# 16_FE_PORT_9-16.net
KiCad netlist of a schematic drawn in Altium Designer
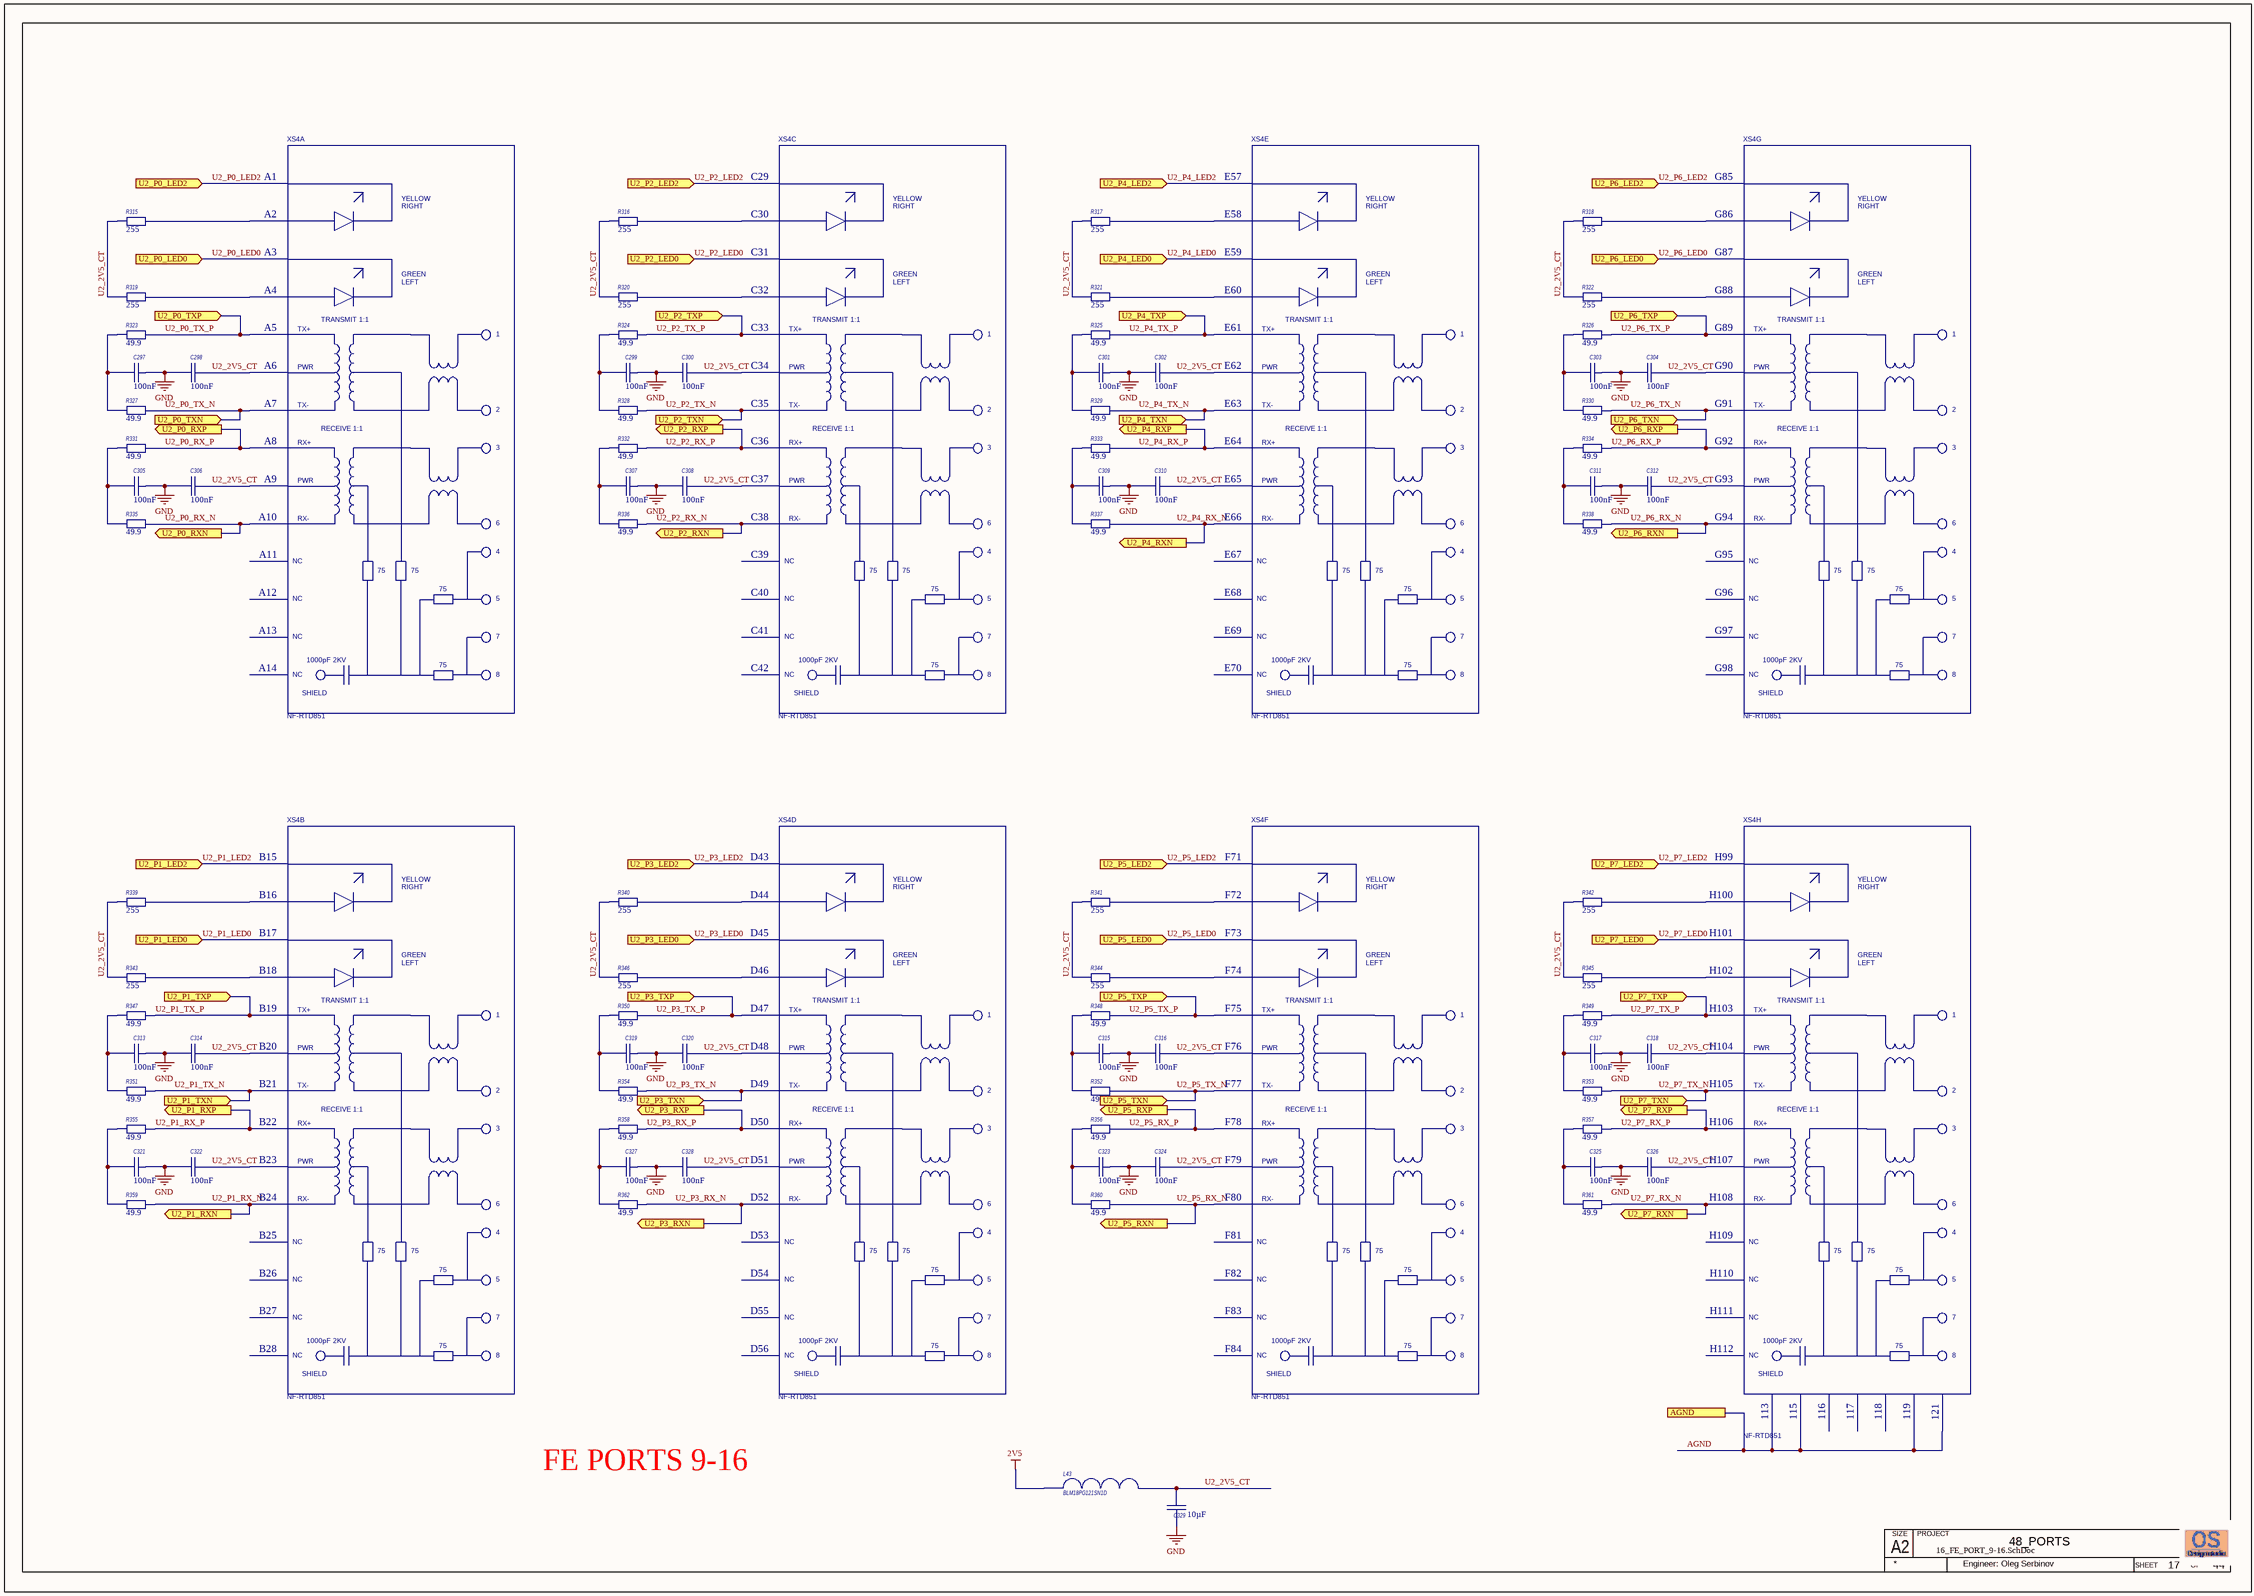
[diagram p0: 16_FE_PORT_9-16.SchDoc]

(export (version "E")
  (design (tool "Eeschema 10.0.6"))
  (components
    (comp (ref "C297")
      (value "GRM155R71E104KE14D")
      (footprint "C0402_IPC High Density")
      (description "C0402, 100nF, 25V, X7R")
      (fields
        (field (name "MANUFACTURER") "Murata")
        (field (name "CAPACITANCE") "100nF")
        (field (name "CUSTOMER PART NUMBER") "Конденсатор, 100n, 0402, 25V, X7R, 10%")
      )
      (libsource (lib "CAPACITORS") (part "GRM155R71E104KE14D"))
    )
    (comp (ref "C298")
      (value "GRM155R71E104KE14D")
      (footprint "C0402_IPC High Density")
      (description "C0402, 100nF, 25V, X7R")
      (fields
        (field (name "MANUFACTURER") "Murata")
        (field (name "CAPACITANCE") "100nF")
        (field (name "CUSTOMER PART NUMBER") "Конденсатор, 100n, 0402, 25V, X7R, 10%")
      )
      (libsource (lib "CAPACITORS") (part "GRM155R71E104KE14D"))
    )
    (comp (ref "C299")
      (value "GRM155R71E104KE14D")
      (footprint "C0402_IPC High Density")
      (description "C0402, 100nF, 25V, X7R")
      (fields
        (field (name "MANUFACTURER") "Murata")
        (field (name "CAPACITANCE") "100nF")
        (field (name "CUSTOMER PART NUMBER") "Конденсатор, 100n, 0402, 25V, X7R, 10%")
      )
      (libsource (lib "CAPACITORS") (part "GRM155R71E104KE14D"))
    )
    (comp (ref "C300")
      (value "GRM155R71E104KE14D")
      (footprint "C0402_IPC High Density")
      (description "C0402, 100nF, 25V, X7R")
      (fields
        (field (name "MANUFACTURER") "Murata")
        (field (name "CAPACITANCE") "100nF")
        (field (name "CUSTOMER PART NUMBER") "Конденсатор, 100n, 0402, 25V, X7R, 10%")
      )
      (libsource (lib "CAPACITORS") (part "GRM155R71E104KE14D"))
    )
    (comp (ref "C301")
      (value "GRM155R71E104KE14D")
      (footprint "C0402_IPC High Density")
      (description "C0402, 100nF, 25V, X7R")
      (fields
        (field (name "MANUFACTURER") "Murata")
        (field (name "CAPACITANCE") "100nF")
        (field (name "CUSTOMER PART NUMBER") "Конденсатор, 100n, 0402, 25V, X7R, 10%")
      )
      (libsource (lib "CAPACITORS") (part "GRM155R71E104KE14D"))
    )
    (comp (ref "C302")
      (value "GRM155R71E104KE14D")
      (footprint "C0402_IPC High Density")
      (description "C0402, 100nF, 25V, X7R")
      (fields
        (field (name "MANUFACTURER") "Murata")
        (field (name "CAPACITANCE") "100nF")
        (field (name "CUSTOMER PART NUMBER") "Конденсатор, 100n, 0402, 25V, X7R, 10%")
      )
      (libsource (lib "CAPACITORS") (part "GRM155R71E104KE14D"))
    )
    (comp (ref "C303")
      (value "GRM155R71E104KE14D")
      (footprint "C0402_IPC High Density")
      (description "C0402, 100nF, 25V, X7R")
      (fields
        (field (name "MANUFACTURER") "Murata")
        (field (name "CAPACITANCE") "100nF")
        (field (name "CUSTOMER PART NUMBER") "Конденсатор, 100n, 0402, 25V, X7R, 10%")
      )
      (libsource (lib "CAPACITORS") (part "GRM155R71E104KE14D"))
    )
    (comp (ref "C304")
      (value "GRM155R71E104KE14D")
      (footprint "C0402_IPC High Density")
      (description "C0402, 100nF, 25V, X7R")
      (fields
        (field (name "MANUFACTURER") "Murata")
        (field (name "CAPACITANCE") "100nF")
        (field (name "CUSTOMER PART NUMBER") "Конденсатор, 100n, 0402, 25V, X7R, 10%")
      )
      (libsource (lib "CAPACITORS") (part "GRM155R71E104KE14D"))
    )
    (comp (ref "C305")
      (value "GRM155R71E104KE14D")
      (footprint "C0402_IPC High Density")
      (description "C0402, 100nF, 25V, X7R")
      (fields
        (field (name "MANUFACTURER") "Murata")
        (field (name "CAPACITANCE") "100nF")
        (field (name "CUSTOMER PART NUMBER") "Конденсатор, 100n, 0402, 25V, X7R, 10%")
      )
      (libsource (lib "CAPACITORS") (part "GRM155R71E104KE14D"))
    )
    (comp (ref "C306")
      (value "GRM155R71E104KE14D")
      (footprint "C0402_IPC High Density")
      (description "C0402, 100nF, 25V, X7R")
      (fields
        (field (name "MANUFACTURER") "Murata")
        (field (name "CAPACITANCE") "100nF")
        (field (name "CUSTOMER PART NUMBER") "Конденсатор, 100n, 0402, 25V, X7R, 10%")
      )
      (libsource (lib "CAPACITORS") (part "GRM155R71E104KE14D"))
    )
    (comp (ref "C307")
      (value "GRM155R71E104KE14D")
      (footprint "C0402_IPC High Density")
      (description "C0402, 100nF, 25V, X7R")
      (fields
        (field (name "MANUFACTURER") "Murata")
        (field (name "CAPACITANCE") "100nF")
        (field (name "CUSTOMER PART NUMBER") "Конденсатор, 100n, 0402, 25V, X7R, 10%")
      )
      (libsource (lib "CAPACITORS") (part "GRM155R71E104KE14D"))
    )
    (comp (ref "C308")
      (value "GRM155R71E104KE14D")
      (footprint "C0402_IPC High Density")
      (description "C0402, 100nF, 25V, X7R")
      (fields
        (field (name "MANUFACTURER") "Murata")
        (field (name "CAPACITANCE") "100nF")
        (field (name "CUSTOMER PART NUMBER") "Конденсатор, 100n, 0402, 25V, X7R, 10%")
      )
      (libsource (lib "CAPACITORS") (part "GRM155R71E104KE14D"))
    )
    (comp (ref "C309")
      (value "GRM155R71E104KE14D")
      (footprint "C0402_IPC High Density")
      (description "C0402, 100nF, 25V, X7R")
      (fields
        (field (name "MANUFACTURER") "Murata")
        (field (name "CAPACITANCE") "100nF")
        (field (name "CUSTOMER PART NUMBER") "Конденсатор, 100n, 0402, 25V, X7R, 10%")
      )
      (libsource (lib "CAPACITORS") (part "GRM155R71E104KE14D"))
    )
    (comp (ref "C310")
      (value "GRM155R71E104KE14D")
      (footprint "C0402_IPC High Density")
      (description "C0402, 100nF, 25V, X7R")
      (fields
        (field (name "MANUFACTURER") "Murata")
        (field (name "CAPACITANCE") "100nF")
        (field (name "CUSTOMER PART NUMBER") "Конденсатор, 100n, 0402, 25V, X7R, 10%")
      )
      (libsource (lib "CAPACITORS") (part "GRM155R71E104KE14D"))
    )
    (comp (ref "C311")
      (value "GRM155R71E104KE14D")
      (footprint "C0402_IPC High Density")
      (description "C0402, 100nF, 25V, X7R")
      (fields
        (field (name "MANUFACTURER") "Murata")
        (field (name "CAPACITANCE") "100nF")
        (field (name "CUSTOMER PART NUMBER") "Конденсатор, 100n, 0402, 25V, X7R, 10%")
      )
      (libsource (lib "CAPACITORS") (part "GRM155R71E104KE14D"))
    )
    (comp (ref "C312")
      (value "GRM155R71E104KE14D")
      (footprint "C0402_IPC High Density")
      (description "C0402, 100nF, 25V, X7R")
      (fields
        (field (name "MANUFACTURER") "Murata")
        (field (name "CAPACITANCE") "100nF")
        (field (name "CUSTOMER PART NUMBER") "Конденсатор, 100n, 0402, 25V, X7R, 10%")
      )
      (libsource (lib "CAPACITORS") (part "GRM155R71E104KE14D"))
    )
    (comp (ref "C313")
      (value "GRM155R71E104KE14D")
      (footprint "C0402_IPC High Density")
      (description "C0402, 100nF, 25V, X7R")
      (fields
        (field (name "MANUFACTURER") "Murata")
        (field (name "CAPACITANCE") "100nF")
        (field (name "CUSTOMER PART NUMBER") "Конденсатор, 100n, 0402, 25V, X7R, 10%")
      )
      (libsource (lib "CAPACITORS") (part "GRM155R71E104KE14D"))
    )
    (comp (ref "C314")
      (value "GRM155R71E104KE14D")
      (footprint "C0402_IPC High Density")
      (description "C0402, 100nF, 25V, X7R")
      (fields
        (field (name "MANUFACTURER") "Murata")
        (field (name "CAPACITANCE") "100nF")
        (field (name "CUSTOMER PART NUMBER") "Конденсатор, 100n, 0402, 25V, X7R, 10%")
      )
      (libsource (lib "CAPACITORS") (part "GRM155R71E104KE14D"))
    )
    (comp (ref "C315")
      (value "GRM155R71E104KE14D")
      (footprint "C0402_IPC High Density")
      (description "C0402, 100nF, 25V, X7R")
      (fields
        (field (name "MANUFACTURER") "Murata")
        (field (name "CAPACITANCE") "100nF")
        (field (name "CUSTOMER PART NUMBER") "Конденсатор, 100n, 0402, 25V, X7R, 10%")
      )
      (libsource (lib "CAPACITORS") (part "GRM155R71E104KE14D"))
    )
    (comp (ref "C316")
      (value "GRM155R71E104KE14D")
      (footprint "C0402_IPC High Density")
      (description "C0402, 100nF, 25V, X7R")
      (fields
        (field (name "MANUFACTURER") "Murata")
        (field (name "CAPACITANCE") "100nF")
        (field (name "CUSTOMER PART NUMBER") "Конденсатор, 100n, 0402, 25V, X7R, 10%")
      )
      (libsource (lib "CAPACITORS") (part "GRM155R71E104KE14D"))
    )
    (comp (ref "C317")
      (value "GRM155R71E104KE14D")
      (footprint "C0402_IPC High Density")
      (description "C0402, 100nF, 25V, X7R")
      (fields
        (field (name "MANUFACTURER") "Murata")
        (field (name "CAPACITANCE") "100nF")
        (field (name "CUSTOMER PART NUMBER") "Конденсатор, 100n, 0402, 25V, X7R, 10%")
      )
      (libsource (lib "CAPACITORS") (part "GRM155R71E104KE14D"))
    )
    (comp (ref "C318")
      (value "GRM155R71E104KE14D")
      (footprint "C0402_IPC High Density")
      (description "C0402, 100nF, 25V, X7R")
      (fields
        (field (name "MANUFACTURER") "Murata")
        (field (name "CAPACITANCE") "100nF")
        (field (name "CUSTOMER PART NUMBER") "Конденсатор, 100n, 0402, 25V, X7R, 10%")
      )
      (libsource (lib "CAPACITORS") (part "GRM155R71E104KE14D"))
    )
    (comp (ref "C319")
      (value "GRM155R71E104KE14D")
      (footprint "C0402_IPC High Density")
      (description "C0402, 100nF, 25V, X7R")
      (fields
        (field (name "MANUFACTURER") "Murata")
        (field (name "CAPACITANCE") "100nF")
        (field (name "CUSTOMER PART NUMBER") "Конденсатор, 100n, 0402, 25V, X7R, 10%")
      )
      (libsource (lib "CAPACITORS") (part "GRM155R71E104KE14D"))
    )
    (comp (ref "C320")
      (value "GRM155R71E104KE14D")
      (footprint "C0402_IPC High Density")
      (description "C0402, 100nF, 25V, X7R")
      (fields
        (field (name "MANUFACTURER") "Murata")
        (field (name "CAPACITANCE") "100nF")
        (field (name "CUSTOMER PART NUMBER") "Конденсатор, 100n, 0402, 25V, X7R, 10%")
      )
      (libsource (lib "CAPACITORS") (part "GRM155R71E104KE14D"))
    )
    (comp (ref "C321")
      (value "GRM155R71E104KE14D")
      (footprint "C0402_IPC High Density")
      (description "C0402, 100nF, 25V, X7R")
      (fields
        (field (name "MANUFACTURER") "Murata")
        (field (name "CAPACITANCE") "100nF")
        (field (name "CUSTOMER PART NUMBER") "Конденсатор, 100n, 0402, 25V, X7R, 10%")
      )
      (libsource (lib "CAPACITORS") (part "GRM155R71E104KE14D"))
    )
    (comp (ref "C322")
      (value "GRM155R71E104KE14D")
      (footprint "C0402_IPC High Density")
      (description "C0402, 100nF, 25V, X7R")
      (fields
        (field (name "MANUFACTURER") "Murata")
        (field (name "CAPACITANCE") "100nF")
        (field (name "CUSTOMER PART NUMBER") "Конденсатор, 100n, 0402, 25V, X7R, 10%")
      )
      (libsource (lib "CAPACITORS") (part "GRM155R71E104KE14D"))
    )
    (comp (ref "C323")
      (value "GRM155R71E104KE14D")
      (footprint "C0402_IPC High Density")
      (description "C0402, 100nF, 25V, X7R")
      (fields
        (field (name "MANUFACTURER") "Murata")
        (field (name "CAPACITANCE") "100nF")
        (field (name "CUSTOMER PART NUMBER") "Конденсатор, 100n, 0402, 25V, X7R, 10%")
      )
      (libsource (lib "CAPACITORS") (part "GRM155R71E104KE14D"))
    )
    (comp (ref "C324")
      (value "GRM155R71E104KE14D")
      (footprint "C0402_IPC High Density")
      (description "C0402, 100nF, 25V, X7R")
      (fields
        (field (name "MANUFACTURER") "Murata")
        (field (name "CAPACITANCE") "100nF")
        (field (name "CUSTOMER PART NUMBER") "Конденсатор, 100n, 0402, 25V, X7R, 10%")
      )
      (libsource (lib "CAPACITORS") (part "GRM155R71E104KE14D"))
    )
    (comp (ref "C325")
      (value "GRM155R71E104KE14D")
      (footprint "C0402_IPC High Density")
      (description "C0402, 100nF, 25V, X7R")
      (fields
        (field (name "MANUFACTURER") "Murata")
        (field (name "CAPACITANCE") "100nF")
        (field (name "CUSTOMER PART NUMBER") "Конденсатор, 100n, 0402, 25V, X7R, 10%")
      )
      (libsource (lib "CAPACITORS") (part "GRM155R71E104KE14D"))
    )
    (comp (ref "C326")
      (value "GRM155R71E104KE14D")
      (footprint "C0402_IPC High Density")
      (description "C0402, 100nF, 25V, X7R")
      (fields
        (field (name "MANUFACTURER") "Murata")
        (field (name "CAPACITANCE") "100nF")
        (field (name "CUSTOMER PART NUMBER") "Конденсатор, 100n, 0402, 25V, X7R, 10%")
      )
      (libsource (lib "CAPACITORS") (part "GRM155R71E104KE14D"))
    )
    (comp (ref "C327")
      (value "GRM155R71E104KE14D")
      (footprint "C0402_IPC High Density")
      (description "C0402, 100nF, 25V, X7R")
      (fields
        (field (name "MANUFACTURER") "Murata")
        (field (name "CAPACITANCE") "100nF")
        (field (name "CUSTOMER PART NUMBER") "Конденсатор, 100n, 0402, 25V, X7R, 10%")
      )
      (libsource (lib "CAPACITORS") (part "GRM155R71E104KE14D"))
    )
    (comp (ref "C328")
      (value "GRM155R71E104KE14D")
      (footprint "C0402_IPC High Density")
      (description "C0402, 100nF, 25V, X7R")
      (fields
        (field (name "MANUFACTURER") "Murata")
        (field (name "CAPACITANCE") "100nF")
        (field (name "CUSTOMER PART NUMBER") "Конденсатор, 100n, 0402, 25V, X7R, 10%")
      )
      (libsource (lib "CAPACITORS") (part "GRM155R71E104KE14D"))
    )
    (comp (ref "C329")
      (value "GRM21BR61C106KE15")
      (footprint "CAPC2012[0805]")
      (description "C0805, 10uF 10%, 16V, X5R")
      (fields
        (field (name "MANUFACTURER") "Murata")
        (field (name "TOLERANCE") "±10%")
        (field (name "CAPACITANCE") "10µF")
      )
      (libsource (lib "CAPACITORS") (part "GRM21BR61C106KE15"))
    )
    (comp (ref "L43")
      (value "BLM18PG121SN1D")
      (footprint "INDC1608X95N")
      (description "FILTER BLM18 (0603, 2A)")
      (fields
        (field (name "MANUFACTURER") "Murata")
        (field (name "RPART NUMBER") "MPZ1608S121ATAH0 ; CIC10P121NC ; MPZ1608S121ATDH5 ; BLM18PG121SH1D ; 742792625")
      )
      (libsource (lib "INDUCTORS") (part "BLM18PG121SN1D"))
    )
    (comp (ref "R315")
      (value "ERJ-2RKF2550X")
      (footprint "RESC1005[0402]")
      (description "R0402, 255R 1%")
      (fields
        (field (name "MANUFACTURER") "Panasonic")
        (field (name "TOLERANCE") "±1%")
        (field (name "RESISTANCE (OHMS)") "255")
      )
      (libsource (lib "RESISTOR") (part "ERJ-2RKF2550X"))
    )
    (comp (ref "R316")
      (value "ERJ-2RKF2550X")
      (footprint "RESC1005[0402]")
      (description "R0402, 255R 1%")
      (fields
        (field (name "MANUFACTURER") "Panasonic")
        (field (name "TOLERANCE") "±1%")
        (field (name "RESISTANCE (OHMS)") "255")
      )
      (libsource (lib "RESISTOR") (part "ERJ-2RKF2550X"))
    )
    (comp (ref "R317")
      (value "ERJ-2RKF2550X")
      (footprint "RESC1005[0402]")
      (description "R0402, 255R 1%")
      (fields
        (field (name "MANUFACTURER") "Panasonic")
        (field (name "TOLERANCE") "±1%")
        (field (name "RESISTANCE (OHMS)") "255")
      )
      (libsource (lib "RESISTOR") (part "ERJ-2RKF2550X"))
    )
    (comp (ref "R318")
      (value "ERJ-2RKF2550X")
      (footprint "RESC1005[0402]")
      (description "R0402, 255R 1%")
      (fields
        (field (name "MANUFACTURER") "Panasonic")
        (field (name "TOLERANCE") "±1%")
        (field (name "RESISTANCE (OHMS)") "255")
      )
      (libsource (lib "RESISTOR") (part "ERJ-2RKF2550X"))
    )
    (comp (ref "R319")
      (value "ERJ-2RKF2550X")
      (footprint "RESC1005[0402]")
      (description "R0402, 255R 1%")
      (fields
        (field (name "MANUFACTURER") "Panasonic")
        (field (name "TOLERANCE") "±1%")
        (field (name "RESISTANCE (OHMS)") "255")
      )
      (libsource (lib "RESISTOR") (part "ERJ-2RKF2550X"))
    )
    (comp (ref "R320")
      (value "ERJ-2RKF2550X")
      (footprint "RESC1005[0402]")
      (description "R0402, 255R 1%")
      (fields
        (field (name "MANUFACTURER") "Panasonic")
        (field (name "TOLERANCE") "±1%")
        (field (name "RESISTANCE (OHMS)") "255")
      )
      (libsource (lib "RESISTOR") (part "ERJ-2RKF2550X"))
    )
    (comp (ref "R321")
      (value "ERJ-2RKF2550X")
      (footprint "RESC1005[0402]")
      (description "R0402, 255R 1%")
      (fields
        (field (name "MANUFACTURER") "Panasonic")
        (field (name "TOLERANCE") "±1%")
        (field (name "RESISTANCE (OHMS)") "255")
      )
      (libsource (lib "RESISTOR") (part "ERJ-2RKF2550X"))
    )
    (comp (ref "R322")
      (value "ERJ-2RKF2550X")
      (footprint "RESC1005[0402]")
      (description "R0402, 255R 1%")
      (fields
        (field (name "MANUFACTURER") "Panasonic")
        (field (name "TOLERANCE") "±1%")
        (field (name "RESISTANCE (OHMS)") "255")
      )
      (libsource (lib "RESISTOR") (part "ERJ-2RKF2550X"))
    )
    (comp (ref "R323")
      (value "ERJ-2RKF49R9X")
      (footprint "R0402_IPC High Density")
      (description "R0402, 49.9R 1%")
      (fields
        (field (name "MANUFACTURER") "Panasonic")
        (field (name "TOLERANCE") "1 %")
        (field (name "RESISTANCE") "49.9")
      )
      (libsource (lib "RESISTOR") (part "ERJ-2RKF49R9X"))
    )
    (comp (ref "R324")
      (value "ERJ-2RKF49R9X")
      (footprint "R0402_IPC High Density")
      (description "R0402, 49.9R 1%")
      (fields
        (field (name "MANUFACTURER") "Panasonic")
        (field (name "TOLERANCE") "1 %")
        (field (name "RESISTANCE") "49.9")
      )
      (libsource (lib "RESISTOR") (part "ERJ-2RKF49R9X"))
    )
    (comp (ref "R325")
      (value "ERJ-2RKF49R9X")
      (footprint "R0402_IPC High Density")
      (description "R0402, 49.9R 1%")
      (fields
        (field (name "MANUFACTURER") "Panasonic")
        (field (name "TOLERANCE") "1 %")
        (field (name "RESISTANCE") "49.9")
      )
      (libsource (lib "RESISTOR") (part "ERJ-2RKF49R9X"))
    )
    (comp (ref "R326")
      (value "ERJ-2RKF49R9X")
      (footprint "R0402_IPC High Density")
      (description "R0402, 49.9R 1%")
      (fields
        (field (name "MANUFACTURER") "Panasonic")
        (field (name "TOLERANCE") "1 %")
        (field (name "RESISTANCE") "49.9")
      )
      (libsource (lib "RESISTOR") (part "ERJ-2RKF49R9X"))
    )
    (comp (ref "R327")
      (value "ERJ-2RKF49R9X")
      (footprint "R0402_IPC High Density")
      (description "R0402, 49.9R 1%")
      (fields
        (field (name "MANUFACTURER") "Panasonic")
        (field (name "TOLERANCE") "1 %")
        (field (name "RESISTANCE") "49.9")
      )
      (libsource (lib "RESISTOR") (part "ERJ-2RKF49R9X"))
    )
    (comp (ref "R328")
      (value "ERJ-2RKF49R9X")
      (footprint "R0402_IPC High Density")
      (description "R0402, 49.9R 1%")
      (fields
        (field (name "MANUFACTURER") "Panasonic")
        (field (name "TOLERANCE") "1 %")
        (field (name "RESISTANCE") "49.9")
      )
      (libsource (lib "RESISTOR") (part "ERJ-2RKF49R9X"))
    )
    (comp (ref "R329")
      (value "ERJ-2RKF49R9X")
      (footprint "R0402_IPC High Density")
      (description "R0402, 49.9R 1%")
      (fields
        (field (name "MANUFACTURER") "Panasonic")
        (field (name "TOLERANCE") "1 %")
        (field (name "RESISTANCE") "49.9")
      )
      (libsource (lib "RESISTOR") (part "ERJ-2RKF49R9X"))
    )
    (comp (ref "R330")
      (value "ERJ-2RKF49R9X")
      (footprint "R0402_IPC High Density")
      (description "R0402, 49.9R 1%")
      (fields
        (field (name "MANUFACTURER") "Panasonic")
        (field (name "TOLERANCE") "1 %")
        (field (name "RESISTANCE") "49.9")
      )
      (libsource (lib "RESISTOR") (part "ERJ-2RKF49R9X"))
    )
    (comp (ref "R331")
      (value "ERJ-2RKF49R9X")
      (footprint "R0402_IPC High Density")
      (description "R0402, 49.9R 1%")
      (fields
        (field (name "MANUFACTURER") "Panasonic")
        (field (name "TOLERANCE") "1 %")
        (field (name "RESISTANCE") "49.9")
      )
      (libsource (lib "RESISTOR") (part "ERJ-2RKF49R9X"))
    )
    (comp (ref "R332")
      (value "ERJ-2RKF49R9X")
      (footprint "R0402_IPC High Density")
      (description "R0402, 49.9R 1%")
      (fields
        (field (name "MANUFACTURER") "Panasonic")
        (field (name "TOLERANCE") "1 %")
        (field (name "RESISTANCE") "49.9")
      )
      (libsource (lib "RESISTOR") (part "ERJ-2RKF49R9X"))
    )
    (comp (ref "R333")
      (value "ERJ-2RKF49R9X")
      (footprint "R0402_IPC High Density")
      (description "R0402, 49.9R 1%")
      (fields
        (field (name "MANUFACTURER") "Panasonic")
        (field (name "TOLERANCE") "1 %")
        (field (name "RESISTANCE") "49.9")
      )
      (libsource (lib "RESISTOR") (part "ERJ-2RKF49R9X"))
    )
    (comp (ref "R334")
      (value "ERJ-2RKF49R9X")
      (footprint "R0402_IPC High Density")
      (description "R0402, 49.9R 1%")
      (fields
        (field (name "MANUFACTURER") "Panasonic")
        (field (name "TOLERANCE") "1 %")
        (field (name "RESISTANCE") "49.9")
      )
      (libsource (lib "RESISTOR") (part "ERJ-2RKF49R9X"))
    )
    (comp (ref "R335")
      (value "ERJ-2RKF49R9X")
      (footprint "R0402_IPC High Density")
      (description "R0402, 49.9R 1%")
      (fields
        (field (name "MANUFACTURER") "Panasonic")
        (field (name "TOLERANCE") "1 %")
        (field (name "RESISTANCE") "49.9")
      )
      (libsource (lib "RESISTOR") (part "ERJ-2RKF49R9X"))
    )
    (comp (ref "R336")
      (value "ERJ-2RKF49R9X")
      (footprint "R0402_IPC High Density")
      (description "R0402, 49.9R 1%")
      (fields
        (field (name "MANUFACTURER") "Panasonic")
        (field (name "TOLERANCE") "1 %")
        (field (name "RESISTANCE") "49.9")
      )
      (libsource (lib "RESISTOR") (part "ERJ-2RKF49R9X"))
    )
    (comp (ref "R337")
      (value "ERJ-2RKF49R9X")
      (footprint "R0402_IPC High Density")
      (description "R0402, 49.9R 1%")
      (fields
        (field (name "MANUFACTURER") "Panasonic")
        (field (name "TOLERANCE") "1 %")
        (field (name "RESISTANCE") "49.9")
      )
      (libsource (lib "RESISTOR") (part "ERJ-2RKF49R9X"))
    )
    (comp (ref "R338")
      (value "ERJ-2RKF49R9X")
      (footprint "R0402_IPC High Density")
      (description "R0402, 49.9R 1%")
      (fields
        (field (name "MANUFACTURER") "Panasonic")
        (field (name "TOLERANCE") "1 %")
        (field (name "RESISTANCE") "49.9")
      )
      (libsource (lib "RESISTOR") (part "ERJ-2RKF49R9X"))
    )
    (comp (ref "R339")
      (value "ERJ-2RKF2550X")
      (footprint "RESC1005[0402]")
      (description "R0402, 255R 1%")
      (fields
        (field (name "MANUFACTURER") "Panasonic")
        (field (name "TOLERANCE") "±1%")
        (field (name "RESISTANCE (OHMS)") "255")
      )
      (libsource (lib "RESISTOR") (part "ERJ-2RKF2550X"))
    )
    (comp (ref "R340")
      (value "ERJ-2RKF2550X")
      (footprint "RESC1005[0402]")
      (description "R0402, 255R 1%")
      (fields
        (field (name "MANUFACTURER") "Panasonic")
        (field (name "TOLERANCE") "±1%")
        (field (name "RESISTANCE (OHMS)") "255")
      )
      (libsource (lib "RESISTOR") (part "ERJ-2RKF2550X"))
    )
    (comp (ref "R341")
      (value "ERJ-2RKF2550X")
      (footprint "RESC1005[0402]")
      (description "R0402, 255R 1%")
      (fields
        (field (name "MANUFACTURER") "Panasonic")
        (field (name "TOLERANCE") "±1%")
        (field (name "RESISTANCE (OHMS)") "255")
      )
      (libsource (lib "RESISTOR") (part "ERJ-2RKF2550X"))
    )
    (comp (ref "R342")
      (value "ERJ-2RKF2550X")
      (footprint "RESC1005[0402]")
      (description "R0402, 255R 1%")
      (fields
        (field (name "MANUFACTURER") "Panasonic")
        (field (name "TOLERANCE") "±1%")
        (field (name "RESISTANCE (OHMS)") "255")
      )
      (libsource (lib "RESISTOR") (part "ERJ-2RKF2550X"))
    )
    (comp (ref "R343")
      (value "ERJ-2RKF2550X")
      (footprint "RESC1005[0402]")
      (description "R0402, 255R 1%")
      (fields
        (field (name "MANUFACTURER") "Panasonic")
        (field (name "TOLERANCE") "±1%")
        (field (name "RESISTANCE (OHMS)") "255")
      )
      (libsource (lib "RESISTOR") (part "ERJ-2RKF2550X"))
    )
    (comp (ref "R344")
      (value "ERJ-2RKF2550X")
      (footprint "RESC1005[0402]")
      (description "R0402, 255R 1%")
      (fields
        (field (name "MANUFACTURER") "Panasonic")
        (field (name "TOLERANCE") "±1%")
        (field (name "RESISTANCE (OHMS)") "255")
      )
      (libsource (lib "RESISTOR") (part "ERJ-2RKF2550X"))
    )
    (comp (ref "R345")
      (value "ERJ-2RKF2550X")
      (footprint "RESC1005[0402]")
      (description "R0402, 255R 1%")
      (fields
        (field (name "MANUFACTURER") "Panasonic")
        (field (name "TOLERANCE") "±1%")
        (field (name "RESISTANCE (OHMS)") "255")
      )
      (libsource (lib "RESISTOR") (part "ERJ-2RKF2550X"))
    )
    (comp (ref "R346")
      (value "ERJ-2RKF2550X")
      (footprint "RESC1005[0402]")
      (description "R0402, 255R 1%")
      (fields
        (field (name "MANUFACTURER") "Panasonic")
        (field (name "TOLERANCE") "±1%")
        (field (name "RESISTANCE (OHMS)") "255")
      )
      (libsource (lib "RESISTOR") (part "ERJ-2RKF2550X"))
    )
    (comp (ref "R347")
      (value "ERJ-2RKF49R9X")
      (footprint "R0402_IPC High Density")
      (description "R0402, 49.9R 1%")
      (fields
        (field (name "MANUFACTURER") "Panasonic")
        (field (name "TOLERANCE") "1 %")
        (field (name "RESISTANCE") "49.9")
      )
      (libsource (lib "RESISTOR") (part "ERJ-2RKF49R9X"))
    )
    (comp (ref "R348")
      (value "ERJ-2RKF49R9X")
      (footprint "R0402_IPC High Density")
      (description "R0402, 49.9R 1%")
      (fields
        (field (name "MANUFACTURER") "Panasonic")
        (field (name "TOLERANCE") "1 %")
        (field (name "RESISTANCE") "49.9")
      )
      (libsource (lib "RESISTOR") (part "ERJ-2RKF49R9X"))
    )
    (comp (ref "R349")
      (value "ERJ-2RKF49R9X")
      (footprint "R0402_IPC High Density")
      (description "R0402, 49.9R 1%")
      (fields
        (field (name "MANUFACTURER") "Panasonic")
        (field (name "TOLERANCE") "1 %")
        (field (name "RESISTANCE") "49.9")
      )
      (libsource (lib "RESISTOR") (part "ERJ-2RKF49R9X"))
    )
    (comp (ref "R350")
      (value "ERJ-2RKF49R9X")
      (footprint "R0402_IPC High Density")
      (description "R0402, 49.9R 1%")
      (fields
        (field (name "MANUFACTURER") "Panasonic")
        (field (name "TOLERANCE") "1 %")
        (field (name "RESISTANCE") "49.9")
      )
      (libsource (lib "RESISTOR") (part "ERJ-2RKF49R9X"))
    )
    (comp (ref "R351")
      (value "ERJ-2RKF49R9X")
      (footprint "R0402_IPC High Density")
      (description "R0402, 49.9R 1%")
      (fields
        (field (name "MANUFACTURER") "Panasonic")
        (field (name "TOLERANCE") "1 %")
        (field (name "RESISTANCE") "49.9")
      )
      (libsource (lib "RESISTOR") (part "ERJ-2RKF49R9X"))
    )
    (comp (ref "R352")
      (value "ERJ-2RKF49R9X")
      (footprint "R0402_IPC High Density")
      (description "R0402, 49.9R 1%")
      (fields
        (field (name "MANUFACTURER") "Panasonic")
        (field (name "TOLERANCE") "1 %")
        (field (name "RESISTANCE") "49.9")
      )
      (libsource (lib "RESISTOR") (part "ERJ-2RKF49R9X"))
    )
    (comp (ref "R353")
      (value "ERJ-2RKF49R9X")
      (footprint "R0402_IPC High Density")
      (description "R0402, 49.9R 1%")
      (fields
        (field (name "MANUFACTURER") "Panasonic")
        (field (name "TOLERANCE") "1 %")
        (field (name "RESISTANCE") "49.9")
      )
      (libsource (lib "RESISTOR") (part "ERJ-2RKF49R9X"))
    )
    (comp (ref "R354")
      (value "ERJ-2RKF49R9X")
      (footprint "R0402_IPC High Density")
      (description "R0402, 49.9R 1%")
      (fields
        (field (name "MANUFACTURER") "Panasonic")
        (field (name "TOLERANCE") "1 %")
        (field (name "RESISTANCE") "49.9")
      )
      (libsource (lib "RESISTOR") (part "ERJ-2RKF49R9X"))
    )
    (comp (ref "R355")
      (value "ERJ-2RKF49R9X")
      (footprint "R0402_IPC High Density")
      (description "R0402, 49.9R 1%")
      (fields
        (field (name "MANUFACTURER") "Panasonic")
        (field (name "TOLERANCE") "1 %")
        (field (name "RESISTANCE") "49.9")
      )
      (libsource (lib "RESISTOR") (part "ERJ-2RKF49R9X"))
    )
    (comp (ref "R356")
      (value "ERJ-2RKF49R9X")
      (footprint "R0402_IPC High Density")
      (description "R0402, 49.9R 1%")
      (fields
        (field (name "MANUFACTURER") "Panasonic")
        (field (name "TOLERANCE") "1 %")
        (field (name "RESISTANCE") "49.9")
      )
      (libsource (lib "RESISTOR") (part "ERJ-2RKF49R9X"))
    )
    (comp (ref "R357")
      (value "ERJ-2RKF49R9X")
      (footprint "R0402_IPC High Density")
      (description "R0402, 49.9R 1%")
      (fields
        (field (name "MANUFACTURER") "Panasonic")
        (field (name "TOLERANCE") "1 %")
        (field (name "RESISTANCE") "49.9")
      )
      (libsource (lib "RESISTOR") (part "ERJ-2RKF49R9X"))
    )
    (comp (ref "R358")
      (value "ERJ-2RKF49R9X")
      (footprint "R0402_IPC High Density")
      (description "R0402, 49.9R 1%")
      (fields
        (field (name "MANUFACTURER") "Panasonic")
        (field (name "TOLERANCE") "1 %")
        (field (name "RESISTANCE") "49.9")
      )
      (libsource (lib "RESISTOR") (part "ERJ-2RKF49R9X"))
    )
    (comp (ref "R359")
      (value "ERJ-2RKF49R9X")
      (footprint "R0402_IPC High Density")
      (description "R0402, 49.9R 1%")
      (fields
        (field (name "MANUFACTURER") "Panasonic")
        (field (name "TOLERANCE") "1 %")
        (field (name "RESISTANCE") "49.9")
      )
      (libsource (lib "RESISTOR") (part "ERJ-2RKF49R9X"))
    )
    (comp (ref "R360")
      (value "ERJ-2RKF49R9X")
      (footprint "R0402_IPC High Density")
      (description "R0402, 49.9R 1%")
      (fields
        (field (name "MANUFACTURER") "Panasonic")
        (field (name "TOLERANCE") "1 %")
        (field (name "RESISTANCE") "49.9")
      )
      (libsource (lib "RESISTOR") (part "ERJ-2RKF49R9X"))
    )
    (comp (ref "R361")
      (value "ERJ-2RKF49R9X")
      (footprint "R0402_IPC High Density")
      (description "R0402, 49.9R 1%")
      (fields
        (field (name "MANUFACTURER") "Panasonic")
        (field (name "TOLERANCE") "1 %")
        (field (name "RESISTANCE") "49.9")
      )
      (libsource (lib "RESISTOR") (part "ERJ-2RKF49R9X"))
    )
    (comp (ref "R362")
      (value "ERJ-2RKF49R9X")
      (footprint "R0402_IPC High Density")
      (description "R0402, 49.9R 1%")
      (fields
        (field (name "MANUFACTURER") "Panasonic")
        (field (name "TOLERANCE") "1 %")
        (field (name "RESISTANCE") "49.9")
      )
      (libsource (lib "RESISTOR") (part "ERJ-2RKF49R9X"))
    )
    (comp (ref "XS4")
      (value "NF-RTD851")
      (footprint "NF-RTD851_2X4_LED_NF-RTD851_2X4_LED(Primary)")
      (description "Connector RJ45 100mb 8 ports and led  NF-RTD851")
      (fields
        (field (name "CUSTOMER PART NUMBER") "Разъем, NF-RTD851, CONN MAGJACK 8PORT 100 BASE-TX")
        (field (name "MANUFACTURER") "Shenzhen Newfly Electronics")
      )
      (libsource (lib "CONNECTORS") (part "NF-RTD851 2X4 EMI LED"))
    )
  )
  (nets
    (net (code "1") (name "/AGND") (class "Default")
      (node (ref "XS4") (pin "113") (pintype "passive"))
      (node (ref "XS4") (pin "115") (pintype "passive"))
      (node (ref "XS4") (pin "119") (pintype "passive"))
      (node (ref "XS4") (pin "121") (pintype "passive"))
    )
    (net (code "2") (name "/U2_2V5_CT") (class "Default")
      (node (ref "C298") (pin "2") (pintype "passive"))
      (node (ref "C300") (pin "2") (pintype "passive"))
      (node (ref "C302") (pin "2") (pintype "passive"))
      (node (ref "C304") (pin "2") (pintype "passive"))
      (node (ref "C306") (pin "2") (pintype "passive"))
      (node (ref "C308") (pin "2") (pintype "passive"))
      (node (ref "C310") (pin "2") (pintype "passive"))
      (node (ref "C312") (pin "2") (pintype "passive"))
      (node (ref "C314") (pin "2") (pintype "passive"))
      (node (ref "C316") (pin "2") (pintype "passive"))
      (node (ref "C318") (pin "2") (pintype "passive"))
      (node (ref "C320") (pin "2") (pintype "passive"))
      (node (ref "C322") (pin "2") (pintype "passive"))
      (node (ref "C324") (pin "2") (pintype "passive"))
      (node (ref "C326") (pin "2") (pintype "passive"))
      (node (ref "C328") (pin "2") (pintype "passive"))
      (node (ref "C329") (pin "2") (pintype "passive"))
      (node (ref "L43") (pin "2") (pinfunction "2_2") (pintype "passive"))
      (node (ref "R315") (pin "1") (pintype "passive"))
      (node (ref "R316") (pin "1") (pintype "passive"))
      (node (ref "R317") (pin "1") (pintype "passive"))
      (node (ref "R318") (pin "1") (pintype "passive"))
      (node (ref "R319") (pin "1") (pintype "passive"))
      (node (ref "R320") (pin "1") (pintype "passive"))
      (node (ref "R321") (pin "1") (pintype "passive"))
      (node (ref "R322") (pin "1") (pintype "passive"))
      (node (ref "R339") (pin "1") (pintype "passive"))
      (node (ref "R340") (pin "1") (pintype "passive"))
      (node (ref "R341") (pin "1") (pintype "passive"))
      (node (ref "R342") (pin "1") (pintype "passive"))
      (node (ref "R343") (pin "1") (pintype "passive"))
      (node (ref "R344") (pin "1") (pintype "passive"))
      (node (ref "R345") (pin "1") (pintype "passive"))
      (node (ref "R346") (pin "1") (pintype "passive"))
      (node (ref "XS4") (pin "A6") (pintype "passive"))
      (node (ref "XS4") (pin "A9") (pintype "passive"))
      (node (ref "XS4") (pin "B20") (pintype "passive"))
      (node (ref "XS4") (pin "B23") (pintype "passive"))
      (node (ref "XS4") (pin "C34") (pintype "passive"))
      (node (ref "XS4") (pin "C37") (pintype "passive"))
      (node (ref "XS4") (pin "D48") (pintype "passive"))
      (node (ref "XS4") (pin "D51") (pintype "passive"))
      (node (ref "XS4") (pin "E62") (pintype "passive"))
      (node (ref "XS4") (pin "E65") (pintype "passive"))
      (node (ref "XS4") (pin "F76") (pintype "passive"))
      (node (ref "XS4") (pin "F79") (pintype "passive"))
      (node (ref "XS4") (pin "G90") (pintype "passive"))
      (node (ref "XS4") (pin "G93") (pintype "passive"))
      (node (ref "XS4") (pin "H104") (pintype "passive"))
      (node (ref "XS4") (pin "H107") (pintype "passive"))
    )
    (net (code "3") (name "/U2_P0_LED0") (class "Default") (node (ref "XS4") (pin "A3") (pintype "passive")))
    (net (code "4") (name "/U2_P0_LED2") (class "Default") (node (ref "XS4") (pin "A1") (pintype "passive")))
    (net (code "5") (name "/U2_P0_RX_N") (class "Default")
      (node (ref "R335") (pin "2") (pintype "passive"))
      (node (ref "XS4") (pin "A10") (pintype "passive"))
    )
    (net (code "6") (name "/U2_P0_RX_P") (class "Default")
      (node (ref "R331") (pin "2") (pintype "passive"))
      (node (ref "XS4") (pin "A8") (pintype "passive"))
    )
    (net (code "7") (name "/U2_P0_TX_N") (class "Default")
      (node (ref "R327") (pin "2") (pintype "passive"))
      (node (ref "XS4") (pin "A7") (pintype "passive"))
    )
    (net (code "8") (name "/U2_P0_TX_P") (class "Default")
      (node (ref "R323") (pin "2") (pintype "passive"))
      (node (ref "XS4") (pin "A5") (pintype "passive"))
    )
    (net (code "9") (name "/U2_P1_LED0") (class "Default") (node (ref "XS4") (pin "B17") (pintype "passive")))
    (net (code "10") (name "/U2_P1_LED2") (class "Default")
      (node (ref "XS4") (pin "B15") (pintype "passive"))
    )
    (net (code "11") (name "/U2_P1_RX_N") (class "Default")
      (node (ref "R359") (pin "2") (pintype "passive"))
      (node (ref "XS4") (pin "B24") (pintype "passive"))
    )
    (net (code "12") (name "/U2_P1_RX_P") (class "Default")
      (node (ref "R355") (pin "2") (pintype "passive"))
      (node (ref "XS4") (pin "B22") (pintype "passive"))
    )
    (net (code "13") (name "/U2_P1_TX_N") (class "Default")
      (node (ref "R351") (pin "2") (pintype "passive"))
      (node (ref "XS4") (pin "B21") (pintype "passive"))
    )
    (net (code "14") (name "/U2_P1_TX_P") (class "Default")
      (node (ref "R347") (pin "2") (pintype "passive"))
      (node (ref "XS4") (pin "B19") (pintype "passive"))
    )
    (net (code "15") (name "/U2_P2_LED0") (class "Default")
      (node (ref "XS4") (pin "C31") (pintype "passive"))
    )
    (net (code "16") (name "/U2_P2_LED2") (class "Default")
      (node (ref "XS4") (pin "C29") (pintype "passive"))
    )
    (net (code "17") (name "/U2_P2_RX_N") (class "Default")
      (node (ref "R336") (pin "2") (pintype "passive"))
      (node (ref "XS4") (pin "C38") (pintype "passive"))
    )
    (net (code "18") (name "/U2_P2_RX_P") (class "Default")
      (node (ref "R332") (pin "2") (pintype "passive"))
      (node (ref "XS4") (pin "C36") (pintype "passive"))
    )
    (net (code "19") (name "/U2_P2_TX_N") (class "Default")
      (node (ref "R328") (pin "2") (pintype "passive"))
      (node (ref "XS4") (pin "C35") (pintype "passive"))
    )
    (net (code "20") (name "/U2_P2_TX_P") (class "Default")
      (node (ref "R324") (pin "2") (pintype "passive"))
      (node (ref "XS4") (pin "C33") (pintype "passive"))
    )
    (net (code "21") (name "/U2_P3_LED0") (class "Default")
      (node (ref "XS4") (pin "D45") (pintype "passive"))
    )
    (net (code "22") (name "/U2_P3_LED2") (class "Default")
      (node (ref "XS4") (pin "D43") (pintype "passive"))
    )
    (net (code "23") (name "/U2_P3_RX_N") (class "Default")
      (node (ref "R362") (pin "2") (pintype "passive"))
      (node (ref "XS4") (pin "D52") (pintype "passive"))
    )
    (net (code "24") (name "/U2_P3_RX_P") (class "Default")
      (node (ref "R358") (pin "2") (pintype "passive"))
      (node (ref "XS4") (pin "D50") (pintype "passive"))
    )
    (net (code "25") (name "/U2_P3_TX_N") (class "Default")
      (node (ref "R354") (pin "2") (pintype "passive"))
      (node (ref "XS4") (pin "D49") (pintype "passive"))
    )
    (net (code "26") (name "/U2_P3_TX_P") (class "Default")
      (node (ref "R350") (pin "2") (pintype "passive"))
      (node (ref "XS4") (pin "D47") (pintype "passive"))
    )
    (net (code "27") (name "/U2_P4_LED0") (class "Default")
      (node (ref "XS4") (pin "E59") (pintype "passive"))
    )
    (net (code "28") (name "/U2_P4_LED2") (class "Default")
      (node (ref "XS4") (pin "E57") (pintype "passive"))
    )
    (net (code "29") (name "/U2_P4_RX_N") (class "Default")
      (node (ref "R337") (pin "2") (pintype "passive"))
      (node (ref "XS4") (pin "E66") (pintype "passive"))
    )
    (net (code "30") (name "/U2_P4_RX_P") (class "Default")
      (node (ref "R333") (pin "2") (pintype "passive"))
      (node (ref "XS4") (pin "E64") (pintype "passive"))
    )
    (net (code "31") (name "/U2_P4_TX_N") (class "Default")
      (node (ref "R329") (pin "2") (pintype "passive"))
      (node (ref "XS4") (pin "E63") (pintype "passive"))
    )
    (net (code "32") (name "/U2_P4_TX_P") (class "Default")
      (node (ref "R325") (pin "2") (pintype "passive"))
      (node (ref "XS4") (pin "E61") (pintype "passive"))
    )
    (net (code "33") (name "/U2_P5_LED0") (class "Default")
      (node (ref "XS4") (pin "F73") (pintype "passive"))
    )
    (net (code "34") (name "/U2_P5_LED2") (class "Default")
      (node (ref "XS4") (pin "F71") (pintype "passive"))
    )
    (net (code "35") (name "/U2_P5_RX_N") (class "Default")
      (node (ref "R360") (pin "2") (pintype "passive"))
      (node (ref "XS4") (pin "F80") (pintype "passive"))
    )
    (net (code "36") (name "/U2_P5_RX_P") (class "Default")
      (node (ref "R356") (pin "2") (pintype "passive"))
      (node (ref "XS4") (pin "F78") (pintype "passive"))
    )
    (net (code "37") (name "/U2_P5_TX_N") (class "Default")
      (node (ref "R352") (pin "2") (pintype "passive"))
      (node (ref "XS4") (pin "F77") (pintype "passive"))
    )
    (net (code "38") (name "/U2_P5_TX_P") (class "Default")
      (node (ref "R348") (pin "2") (pintype "passive"))
      (node (ref "XS4") (pin "F75") (pintype "passive"))
    )
    (net (code "39") (name "/U2_P6_LED0") (class "Default")
      (node (ref "XS4") (pin "G87") (pintype "passive"))
    )
    (net (code "40") (name "/U2_P6_LED2") (class "Default")
      (node (ref "XS4") (pin "G85") (pintype "passive"))
    )
    (net (code "41") (name "/U2_P6_RX_N") (class "Default")
      (node (ref "R338") (pin "2") (pintype "passive"))
      (node (ref "XS4") (pin "G94") (pintype "passive"))
    )
    (net (code "42") (name "/U2_P6_RX_P") (class "Default")
      (node (ref "R334") (pin "2") (pintype "passive"))
      (node (ref "XS4") (pin "G92") (pintype "passive"))
    )
    (net (code "43") (name "/U2_P6_TX_N") (class "Default")
      (node (ref "R330") (pin "2") (pintype "passive"))
      (node (ref "XS4") (pin "G91") (pintype "passive"))
    )
    (net (code "44") (name "/U2_P6_TX_P") (class "Default")
      (node (ref "R326") (pin "2") (pintype "passive"))
      (node (ref "XS4") (pin "G89") (pintype "passive"))
    )
    (net (code "45") (name "/U2_P7_LED0") (class "Default")
      (node (ref "XS4") (pin "H101") (pintype "passive"))
    )
    (net (code "46") (name "/U2_P7_LED2") (class "Default")
      (node (ref "XS4") (pin "H99") (pintype "passive"))
    )
    (net (code "47") (name "/U2_P7_RX_N") (class "Default")
      (node (ref "R361") (pin "2") (pintype "passive"))
      (node (ref "XS4") (pin "H108") (pintype "passive"))
    )
    (net (code "48") (name "/U2_P7_RX_P") (class "Default")
      (node (ref "R357") (pin "2") (pintype "passive"))
      (node (ref "XS4") (pin "H106") (pintype "passive"))
    )
    (net (code "49") (name "/U2_P7_TX_N") (class "Default")
      (node (ref "R353") (pin "2") (pintype "passive"))
      (node (ref "XS4") (pin "H105") (pintype "passive"))
    )
    (net (code "50") (name "/U2_P7_TX_P") (class "Default")
      (node (ref "R349") (pin "2") (pintype "passive"))
      (node (ref "XS4") (pin "H103") (pintype "passive"))
    )
    (net (code "51") (name "2V5") (class "Default")
      (node (ref "L43") (pin "1") (pinfunction "1_1") (pintype "passive"))
    )
    (net (code "52") (name "GND") (class "Default")
      (node (ref "C297") (pin "2") (pintype "passive"))
      (node (ref "C298") (pin "1") (pintype "passive"))
      (node (ref "C299") (pin "2") (pintype "passive"))
      (node (ref "C300") (pin "1") (pintype "passive"))
      (node (ref "C301") (pin "2") (pintype "passive"))
      (node (ref "C302") (pin "1") (pintype "passive"))
      (node (ref "C303") (pin "2") (pintype "passive"))
      (node (ref "C304") (pin "1") (pintype "passive"))
      (node (ref "C305") (pin "2") (pintype "passive"))
      (node (ref "C306") (pin "1") (pintype "passive"))
      (node (ref "C307") (pin "2") (pintype "passive"))
      (node (ref "C308") (pin "1") (pintype "passive"))
      (node (ref "C309") (pin "2") (pintype "passive"))
      (node (ref "C310") (pin "1") (pintype "passive"))
      (node (ref "C311") (pin "2") (pintype "passive"))
      (node (ref "C312") (pin "1") (pintype "passive"))
      (node (ref "C313") (pin "2") (pintype "passive"))
      (node (ref "C314") (pin "1") (pintype "passive"))
      (node (ref "C315") (pin "2") (pintype "passive"))
      (node (ref "C316") (pin "1") (pintype "passive"))
      (node (ref "C317") (pin "2") (pintype "passive"))
      (node (ref "C318") (pin "1") (pintype "passive"))
      (node (ref "C319") (pin "2") (pintype "passive"))
      (node (ref "C320") (pin "1") (pintype "passive"))
      (node (ref "C321") (pin "2") (pintype "passive"))
      (node (ref "C322") (pin "1") (pintype "passive"))
      (node (ref "C323") (pin "2") (pintype "passive"))
      (node (ref "C324") (pin "1") (pintype "passive"))
      (node (ref "C325") (pin "2") (pintype "passive"))
      (node (ref "C326") (pin "1") (pintype "passive"))
      (node (ref "C327") (pin "2") (pintype "passive"))
      (node (ref "C328") (pin "1") (pintype "passive"))
      (node (ref "C329") (pin "1") (pintype "passive"))
    )
    (net (code "53") (name "Net-(C297-Pad1)") (class "Default")
      (node (ref "C297") (pin "1") (pintype "passive"))
      (node (ref "R323") (pin "1") (pintype "passive"))
      (node (ref "R327") (pin "1") (pintype "passive"))
    )
    (net (code "54") (name "Net-(C299-Pad1)") (class "Default")
      (node (ref "C299") (pin "1") (pintype "passive"))
      (node (ref "R324") (pin "1") (pintype "passive"))
      (node (ref "R328") (pin "1") (pintype "passive"))
    )
    (net (code "55") (name "Net-(C301-Pad1)") (class "Default")
      (node (ref "C301") (pin "1") (pintype "passive"))
      (node (ref "R325") (pin "1") (pintype "passive"))
      (node (ref "R329") (pin "1") (pintype "passive"))
    )
    (net (code "56") (name "Net-(C303-Pad1)") (class "Default")
      (node (ref "C303") (pin "1") (pintype "passive"))
      (node (ref "R326") (pin "1") (pintype "passive"))
      (node (ref "R330") (pin "1") (pintype "passive"))
    )
    (net (code "57") (name "Net-(C305-Pad1)") (class "Default")
      (node (ref "C305") (pin "1") (pintype "passive"))
      (node (ref "R331") (pin "1") (pintype "passive"))
      (node (ref "R335") (pin "1") (pintype "passive"))
    )
    (net (code "58") (name "Net-(C307-Pad1)") (class "Default")
      (node (ref "C307") (pin "1") (pintype "passive"))
      (node (ref "R332") (pin "1") (pintype "passive"))
      (node (ref "R336") (pin "1") (pintype "passive"))
    )
    (net (code "59") (name "Net-(C309-Pad1)") (class "Default")
      (node (ref "C309") (pin "1") (pintype "passive"))
      (node (ref "R333") (pin "1") (pintype "passive"))
      (node (ref "R337") (pin "1") (pintype "passive"))
    )
    (net (code "60") (name "Net-(C311-Pad1)") (class "Default")
      (node (ref "C311") (pin "1") (pintype "passive"))
      (node (ref "R334") (pin "1") (pintype "passive"))
      (node (ref "R338") (pin "1") (pintype "passive"))
    )
    (net (code "61") (name "Net-(C313-Pad1)") (class "Default")
      (node (ref "C313") (pin "1") (pintype "passive"))
      (node (ref "R347") (pin "1") (pintype "passive"))
      (node (ref "R351") (pin "1") (pintype "passive"))
    )
    (net (code "62") (name "Net-(C315-Pad1)") (class "Default")
      (node (ref "C315") (pin "1") (pintype "passive"))
      (node (ref "R348") (pin "1") (pintype "passive"))
      (node (ref "R352") (pin "1") (pintype "passive"))
    )
    (net (code "63") (name "Net-(C317-Pad1)") (class "Default")
      (node (ref "C317") (pin "1") (pintype "passive"))
      (node (ref "R349") (pin "1") (pintype "passive"))
      (node (ref "R353") (pin "1") (pintype "passive"))
    )
    (net (code "64") (name "Net-(C319-Pad1)") (class "Default")
      (node (ref "C319") (pin "1") (pintype "passive"))
      (node (ref "R350") (pin "1") (pintype "passive"))
      (node (ref "R354") (pin "1") (pintype "passive"))
    )
    (net (code "65") (name "Net-(C321-Pad1)") (class "Default")
      (node (ref "C321") (pin "1") (pintype "passive"))
      (node (ref "R355") (pin "1") (pintype "passive"))
      (node (ref "R359") (pin "1") (pintype "passive"))
    )
    (net (code "66") (name "Net-(C323-Pad1)") (class "Default")
      (node (ref "C323") (pin "1") (pintype "passive"))
      (node (ref "R356") (pin "1") (pintype "passive"))
      (node (ref "R360") (pin "1") (pintype "passive"))
    )
    (net (code "67") (name "Net-(C325-Pad1)") (class "Default")
      (node (ref "C325") (pin "1") (pintype "passive"))
      (node (ref "R357") (pin "1") (pintype "passive"))
      (node (ref "R361") (pin "1") (pintype "passive"))
    )
    (net (code "68") (name "Net-(C327-Pad1)") (class "Default")
      (node (ref "C327") (pin "1") (pintype "passive"))
      (node (ref "R358") (pin "1") (pintype "passive"))
      (node (ref "R362") (pin "1") (pintype "passive"))
    )
    (net (code "69") (name "Net-(R315-Pad2)") (class "Default")
      (node (ref "R315") (pin "2") (pintype "passive"))
      (node (ref "XS4") (pin "A2") (pintype "passive"))
    )
    (net (code "70") (name "Net-(R316-Pad2)") (class "Default")
      (node (ref "R316") (pin "2") (pintype "passive"))
      (node (ref "XS4") (pin "C30") (pintype "passive"))
    )
    (net (code "71") (name "Net-(R317-Pad2)") (class "Default")
      (node (ref "R317") (pin "2") (pintype "passive"))
      (node (ref "XS4") (pin "E58") (pintype "passive"))
    )
    (net (code "72") (name "Net-(R318-Pad2)") (class "Default")
      (node (ref "R318") (pin "2") (pintype "passive"))
      (node (ref "XS4") (pin "G86") (pintype "passive"))
    )
    (net (code "73") (name "Net-(R319-Pad2)") (class "Default")
      (node (ref "R319") (pin "2") (pintype "passive"))
      (node (ref "XS4") (pin "A4") (pintype "passive"))
    )
    (net (code "74") (name "Net-(R320-Pad2)") (class "Default")
      (node (ref "R320") (pin "2") (pintype "passive"))
      (node (ref "XS4") (pin "C32") (pintype "passive"))
    )
    (net (code "75") (name "Net-(R321-Pad2)") (class "Default")
      (node (ref "R321") (pin "2") (pintype "passive"))
      (node (ref "XS4") (pin "E60") (pintype "passive"))
    )
    (net (code "76") (name "Net-(R322-Pad2)") (class "Default")
      (node (ref "R322") (pin "2") (pintype "passive"))
      (node (ref "XS4") (pin "G88") (pintype "passive"))
    )
    (net (code "77") (name "Net-(R339-Pad2)") (class "Default")
      (node (ref "R339") (pin "2") (pintype "passive"))
      (node (ref "XS4") (pin "B16") (pintype "passive"))
    )
    (net (code "78") (name "Net-(R340-Pad2)") (class "Default")
      (node (ref "R340") (pin "2") (pintype "passive"))
      (node (ref "XS4") (pin "D44") (pintype "passive"))
    )
    (net (code "79") (name "Net-(R341-Pad2)") (class "Default")
      (node (ref "R341") (pin "2") (pintype "passive"))
      (node (ref "XS4") (pin "F72") (pintype "passive"))
    )
    (net (code "80") (name "Net-(R342-Pad2)") (class "Default")
      (node (ref "R342") (pin "2") (pintype "passive"))
      (node (ref "XS4") (pin "H100") (pintype "passive"))
    )
    (net (code "81") (name "Net-(R343-Pad2)") (class "Default")
      (node (ref "R343") (pin "2") (pintype "passive"))
      (node (ref "XS4") (pin "B18") (pintype "passive"))
    )
    (net (code "82") (name "Net-(R344-Pad2)") (class "Default")
      (node (ref "R344") (pin "2") (pintype "passive"))
      (node (ref "XS4") (pin "F74") (pintype "passive"))
    )
    (net (code "83") (name "Net-(R345-Pad2)") (class "Default")
      (node (ref "R345") (pin "2") (pintype "passive"))
      (node (ref "XS4") (pin "H102") (pintype "passive"))
    )
    (net (code "84") (name "Net-(R346-Pad2)") (class "Default")
      (node (ref "R346") (pin "2") (pintype "passive"))
      (node (ref "XS4") (pin "D46") (pintype "passive"))
    )
    (net (code "85") (name "unconnected-(XS4-Pad113)") (class "Default")
      (node (ref "XS4") (pin "113") (pintype "passive"))
    )
    (net (code "86") (name "unconnected-(XS4-Pad113)_1") (class "Default")
      (node (ref "XS4") (pin "113") (pintype "passive"))
    )
    (net (code "87") (name "unconnected-(XS4-Pad113)_2") (class "Default")
      (node (ref "XS4") (pin "113") (pintype "passive"))
    )
    (net (code "88") (name "unconnected-(XS4-Pad113)_3") (class "Default")
      (node (ref "XS4") (pin "113") (pintype "passive"))
    )
    (net (code "89") (name "unconnected-(XS4-Pad113)_4") (class "Default")
      (node (ref "XS4") (pin "113") (pintype "passive"))
    )
    (net (code "90") (name "unconnected-(XS4-Pad113)_5") (class "Default")
      (node (ref "XS4") (pin "113") (pintype "passive"))
    )
    (net (code "91") (name "unconnected-(XS4-Pad113)_6") (class "Default")
      (node (ref "XS4") (pin "113") (pintype "passive"))
    )
    (net (code "92") (name "unconnected-(XS4-Pad113)_7") (class "Default")
      (node (ref "XS4") (pin "113") (pintype "passive"))
    )
    (net (code "93") (name "unconnected-(XS4-Pad114)") (class "Default")
      (node (ref "XS4") (pin "114") (pintype "passive"))
    )
    (net (code "94") (name "unconnected-(XS4-Pad114)_1") (class "Default")
      (node (ref "XS4") (pin "114") (pintype "passive"))
    )
    (net (code "95") (name "unconnected-(XS4-Pad114)_2") (class "Default")
      (node (ref "XS4") (pin "114") (pintype "passive"))
    )
    (net (code "96") (name "unconnected-(XS4-Pad114)_3") (class "Default")
      (node (ref "XS4") (pin "114") (pintype "passive"))
    )
    (net (code "97") (name "unconnected-(XS4-Pad114)_4") (class "Default")
      (node (ref "XS4") (pin "114") (pintype "passive"))
    )
    (net (code "98") (name "unconnected-(XS4-Pad114)_5") (class "Default")
      (node (ref "XS4") (pin "114") (pintype "passive"))
    )
    (net (code "99") (name "unconnected-(XS4-Pad114)_6") (class "Default")
      (node (ref "XS4") (pin "114") (pintype "passive"))
    )
    (net (code "100") (name "unconnected-(XS4-Pad114)_7") (class "Default")
      (node (ref "XS4") (pin "114") (pintype "passive"))
    )
    (net (code "101") (name "unconnected-(XS4-Pad115)") (class "Default")
      (node (ref "XS4") (pin "115") (pintype "passive"))
    )
    (net (code "102") (name "unconnected-(XS4-Pad115)_1") (class "Default")
      (node (ref "XS4") (pin "115") (pintype "passive"))
    )
    (net (code "103") (name "unconnected-(XS4-Pad115)_2") (class "Default")
      (node (ref "XS4") (pin "115") (pintype "passive"))
    )
    (net (code "104") (name "unconnected-(XS4-Pad115)_3") (class "Default")
      (node (ref "XS4") (pin "115") (pintype "passive"))
    )
    (net (code "105") (name "unconnected-(XS4-Pad115)_4") (class "Default")
      (node (ref "XS4") (pin "115") (pintype "passive"))
    )
    (net (code "106") (name "unconnected-(XS4-Pad115)_5") (class "Default")
      (node (ref "XS4") (pin "115") (pintype "passive"))
    )
    (net (code "107") (name "unconnected-(XS4-Pad115)_6") (class "Default")
      (node (ref "XS4") (pin "115") (pintype "passive"))
    )
    (net (code "108") (name "unconnected-(XS4-Pad115)_7") (class "Default")
      (node (ref "XS4") (pin "115") (pintype "passive"))
    )
    (net (code "109") (name "unconnected-(XS4-Pad116)") (class "Default")
      (node (ref "XS4") (pin "116") (pintype "passive"))
    )
    (net (code "110") (name "unconnected-(XS4-Pad116)_1") (class "Default")
      (node (ref "XS4") (pin "116") (pintype "passive"))
    )
    (net (code "111") (name "unconnected-(XS4-Pad116)_2") (class "Default")
      (node (ref "XS4") (pin "116") (pintype "passive"))
    )
    (net (code "112") (name "unconnected-(XS4-Pad116)_3") (class "Default")
      (node (ref "XS4") (pin "116") (pintype "passive"))
    )
    (net (code "113") (name "unconnected-(XS4-Pad116)_4") (class "Default")
      (node (ref "XS4") (pin "116") (pintype "passive"))
    )
    (net (code "114") (name "unconnected-(XS4-Pad116)_5") (class "Default")
      (node (ref "XS4") (pin "116") (pintype "passive"))
    )
    (net (code "115") (name "unconnected-(XS4-Pad116)_6") (class "Default")
      (node (ref "XS4") (pin "116") (pintype "passive"))
    )
    (net (code "116") (name "unconnected-(XS4-Pad116)_7") (class "Default")
      (node (ref "XS4") (pin "116") (pintype "passive"))
    )
    (net (code "117") (name "unconnected-(XS4-Pad116)_8") (class "Default")
      (node (ref "XS4") (pin "116") (pintype "passive"))
    )
    (net (code "118") (name "unconnected-(XS4-Pad117)") (class "Default")
      (node (ref "XS4") (pin "117") (pintype "passive"))
    )
    (net (code "119") (name "unconnected-(XS4-Pad117)_1") (class "Default")
      (node (ref "XS4") (pin "117") (pintype "passive"))
    )
    (net (code "120") (name "unconnected-(XS4-Pad117)_2") (class "Default")
      (node (ref "XS4") (pin "117") (pintype "passive"))
    )
    (net (code "121") (name "unconnected-(XS4-Pad117)_3") (class "Default")
      (node (ref "XS4") (pin "117") (pintype "passive"))
    )
    (net (code "122") (name "unconnected-(XS4-Pad117)_4") (class "Default")
      (node (ref "XS4") (pin "117") (pintype "passive"))
    )
    (net (code "123") (name "unconnected-(XS4-Pad117)_5") (class "Default")
      (node (ref "XS4") (pin "117") (pintype "passive"))
    )
    (net (code "124") (name "unconnected-(XS4-Pad117)_6") (class "Default")
      (node (ref "XS4") (pin "117") (pintype "passive"))
    )
    (net (code "125") (name "unconnected-(XS4-Pad117)_7") (class "Default")
      (node (ref "XS4") (pin "117") (pintype "passive"))
    )
    (net (code "126") (name "unconnected-(XS4-Pad117)_8") (class "Default")
      (node (ref "XS4") (pin "117") (pintype "passive"))
    )
    (net (code "127") (name "unconnected-(XS4-Pad118)") (class "Default")
      (node (ref "XS4") (pin "118") (pintype "passive"))
    )
    (net (code "128") (name "unconnected-(XS4-Pad118)_1") (class "Default")
      (node (ref "XS4") (pin "118") (pintype "passive"))
    )
    (net (code "129") (name "unconnected-(XS4-Pad118)_2") (class "Default")
      (node (ref "XS4") (pin "118") (pintype "passive"))
    )
    (net (code "130") (name "unconnected-(XS4-Pad118)_3") (class "Default")
      (node (ref "XS4") (pin "118") (pintype "passive"))
    )
    (net (code "131") (name "unconnected-(XS4-Pad118)_4") (class "Default")
      (node (ref "XS4") (pin "118") (pintype "passive"))
    )
    (net (code "132") (name "unconnected-(XS4-Pad118)_5") (class "Default")
      (node (ref "XS4") (pin "118") (pintype "passive"))
    )
    (net (code "133") (name "unconnected-(XS4-Pad118)_6") (class "Default")
      (node (ref "XS4") (pin "118") (pintype "passive"))
    )
    (net (code "134") (name "unconnected-(XS4-Pad118)_7") (class "Default")
      (node (ref "XS4") (pin "118") (pintype "passive"))
    )
    (net (code "135") (name "unconnected-(XS4-Pad118)_8") (class "Default")
      (node (ref "XS4") (pin "118") (pintype "passive"))
    )
    (net (code "136") (name "unconnected-(XS4-Pad119)") (class "Default")
      (node (ref "XS4") (pin "119") (pintype "passive"))
    )
    (net (code "137") (name "unconnected-(XS4-Pad119)_1") (class "Default")
      (node (ref "XS4") (pin "119") (pintype "passive"))
    )
    (net (code "138") (name "unconnected-(XS4-Pad119)_2") (class "Default")
      (node (ref "XS4") (pin "119") (pintype "passive"))
    )
    (net (code "139") (name "unconnected-(XS4-Pad119)_3") (class "Default")
      (node (ref "XS4") (pin "119") (pintype "passive"))
    )
    (net (code "140") (name "unconnected-(XS4-Pad119)_4") (class "Default")
      (node (ref "XS4") (pin "119") (pintype "passive"))
    )
    (net (code "141") (name "unconnected-(XS4-Pad119)_5") (class "Default")
      (node (ref "XS4") (pin "119") (pintype "passive"))
    )
    (net (code "142") (name "unconnected-(XS4-Pad119)_6") (class "Default")
      (node (ref "XS4") (pin "119") (pintype "passive"))
    )
    (net (code "143") (name "unconnected-(XS4-Pad119)_7") (class "Default")
      (node (ref "XS4") (pin "119") (pintype "passive"))
    )
    (net (code "144") (name "unconnected-(XS4-Pad120)") (class "Default")
      (node (ref "XS4") (pin "120") (pintype "passive"))
    )
    (net (code "145") (name "unconnected-(XS4-Pad120)_1") (class "Default")
      (node (ref "XS4") (pin "120") (pintype "passive"))
    )
    (net (code "146") (name "unconnected-(XS4-Pad120)_2") (class "Default")
      (node (ref "XS4") (pin "120") (pintype "passive"))
    )
    (net (code "147") (name "unconnected-(XS4-Pad120)_3") (class "Default")
      (node (ref "XS4") (pin "120") (pintype "passive"))
    )
    (net (code "148") (name "unconnected-(XS4-Pad120)_4") (class "Default")
      (node (ref "XS4") (pin "120") (pintype "passive"))
    )
    (net (code "149") (name "unconnected-(XS4-Pad120)_5") (class "Default")
      (node (ref "XS4") (pin "120") (pintype "passive"))
    )
    (net (code "150") (name "unconnected-(XS4-Pad120)_6") (class "Default")
      (node (ref "XS4") (pin "120") (pintype "passive"))
    )
    (net (code "151") (name "unconnected-(XS4-Pad120)_7") (class "Default")
      (node (ref "XS4") (pin "120") (pintype "passive"))
    )
    (net (code "152") (name "unconnected-(XS4-Pad121)") (class "Default")
      (node (ref "XS4") (pin "121") (pintype "passive"))
    )
    (net (code "153") (name "unconnected-(XS4-Pad121)_1") (class "Default")
      (node (ref "XS4") (pin "121") (pintype "passive"))
    )
    (net (code "154") (name "unconnected-(XS4-Pad121)_2") (class "Default")
      (node (ref "XS4") (pin "121") (pintype "passive"))
    )
    (net (code "155") (name "unconnected-(XS4-Pad121)_3") (class "Default")
      (node (ref "XS4") (pin "121") (pintype "passive"))
    )
    (net (code "156") (name "unconnected-(XS4-Pad121)_4") (class "Default")
      (node (ref "XS4") (pin "121") (pintype "passive"))
    )
    (net (code "157") (name "unconnected-(XS4-Pad121)_5") (class "Default")
      (node (ref "XS4") (pin "121") (pintype "passive"))
    )
    (net (code "158") (name "unconnected-(XS4-Pad121)_6") (class "Default")
      (node (ref "XS4") (pin "121") (pintype "passive"))
    )
    (net (code "159") (name "unconnected-(XS4-Pad121)_7") (class "Default")
      (node (ref "XS4") (pin "121") (pintype "passive"))
    )
    (net (code "160") (name "unconnected-(XS4-PadA11)") (class "Default")
      (node (ref "XS4") (pin "A11") (pintype "passive"))
    )
    (net (code "161") (name "unconnected-(XS4-PadA12)") (class "Default")
      (node (ref "XS4") (pin "A12") (pintype "passive"))
    )
    (net (code "162") (name "unconnected-(XS4-PadA13)") (class "Default")
      (node (ref "XS4") (pin "A13") (pintype "passive"))
    )
    (net (code "163") (name "unconnected-(XS4-PadA14)") (class "Default")
      (node (ref "XS4") (pin "A14") (pintype "passive"))
    )
    (net (code "164") (name "unconnected-(XS4-PadB25)") (class "Default")
      (node (ref "XS4") (pin "B25") (pintype "passive"))
    )
    (net (code "165") (name "unconnected-(XS4-PadB26)") (class "Default")
      (node (ref "XS4") (pin "B26") (pintype "passive"))
    )
    (net (code "166") (name "unconnected-(XS4-PadB27)") (class "Default")
      (node (ref "XS4") (pin "B27") (pintype "passive"))
    )
    (net (code "167") (name "unconnected-(XS4-PadB28)") (class "Default")
      (node (ref "XS4") (pin "B28") (pintype "passive"))
    )
    (net (code "168") (name "unconnected-(XS4-PadC39)") (class "Default")
      (node (ref "XS4") (pin "C39") (pintype "passive"))
    )
    (net (code "169") (name "unconnected-(XS4-PadC40)") (class "Default")
      (node (ref "XS4") (pin "C40") (pintype "passive"))
    )
    (net (code "170") (name "unconnected-(XS4-PadC41)") (class "Default")
      (node (ref "XS4") (pin "C41") (pintype "passive"))
    )
    (net (code "171") (name "unconnected-(XS4-PadC42)") (class "Default")
      (node (ref "XS4") (pin "C42") (pintype "passive"))
    )
    (net (code "172") (name "unconnected-(XS4-PadD53)") (class "Default")
      (node (ref "XS4") (pin "D53") (pintype "passive"))
    )
    (net (code "173") (name "unconnected-(XS4-PadD54)") (class "Default")
      (node (ref "XS4") (pin "D54") (pintype "passive"))
    )
    (net (code "174") (name "unconnected-(XS4-PadD55)") (class "Default")
      (node (ref "XS4") (pin "D55") (pintype "passive"))
    )
    (net (code "175") (name "unconnected-(XS4-PadD56)") (class "Default")
      (node (ref "XS4") (pin "D56") (pintype "passive"))
    )
    (net (code "176") (name "unconnected-(XS4-PadE67)") (class "Default")
      (node (ref "XS4") (pin "E67") (pintype "passive"))
    )
    (net (code "177") (name "unconnected-(XS4-PadE68)") (class "Default")
      (node (ref "XS4") (pin "E68") (pintype "passive"))
    )
    (net (code "178") (name "unconnected-(XS4-PadE69)") (class "Default")
      (node (ref "XS4") (pin "E69") (pintype "passive"))
    )
    (net (code "179") (name "unconnected-(XS4-PadE70)") (class "Default")
      (node (ref "XS4") (pin "E70") (pintype "passive"))
    )
    (net (code "180") (name "unconnected-(XS4-PadF81)") (class "Default")
      (node (ref "XS4") (pin "F81") (pintype "passive"))
    )
    (net (code "181") (name "unconnected-(XS4-PadF82)") (class "Default")
      (node (ref "XS4") (pin "F82") (pintype "passive"))
    )
    (net (code "182") (name "unconnected-(XS4-PadF83)") (class "Default")
      (node (ref "XS4") (pin "F83") (pintype "passive"))
    )
    (net (code "183") (name "unconnected-(XS4-PadF84)") (class "Default")
      (node (ref "XS4") (pin "F84") (pintype "passive"))
    )
    (net (code "184") (name "unconnected-(XS4-PadG95)") (class "Default")
      (node (ref "XS4") (pin "G95") (pintype "passive"))
    )
    (net (code "185") (name "unconnected-(XS4-PadG96)") (class "Default")
      (node (ref "XS4") (pin "G96") (pintype "passive"))
    )
    (net (code "186") (name "unconnected-(XS4-PadG97)") (class "Default")
      (node (ref "XS4") (pin "G97") (pintype "passive"))
    )
    (net (code "187") (name "unconnected-(XS4-PadG98)") (class "Default")
      (node (ref "XS4") (pin "G98") (pintype "passive"))
    )
    (net (code "188") (name "unconnected-(XS4-PadH109)") (class "Default")
      (node (ref "XS4") (pin "H109") (pintype "passive"))
    )
    (net (code "189") (name "unconnected-(XS4-PadH110)") (class "Default")
      (node (ref "XS4") (pin "H110") (pintype "passive"))
    )
    (net (code "190") (name "unconnected-(XS4-PadH111)") (class "Default")
      (node (ref "XS4") (pin "H111") (pintype "passive"))
    )
    (net (code "191") (name "unconnected-(XS4-PadH112)") (class "Default")
      (node (ref "XS4") (pin "H112") (pintype "passive"))
    )
  )
)
